# driver-power-stage.net
KiCad netlist of a schematic drawn in Altium Designer
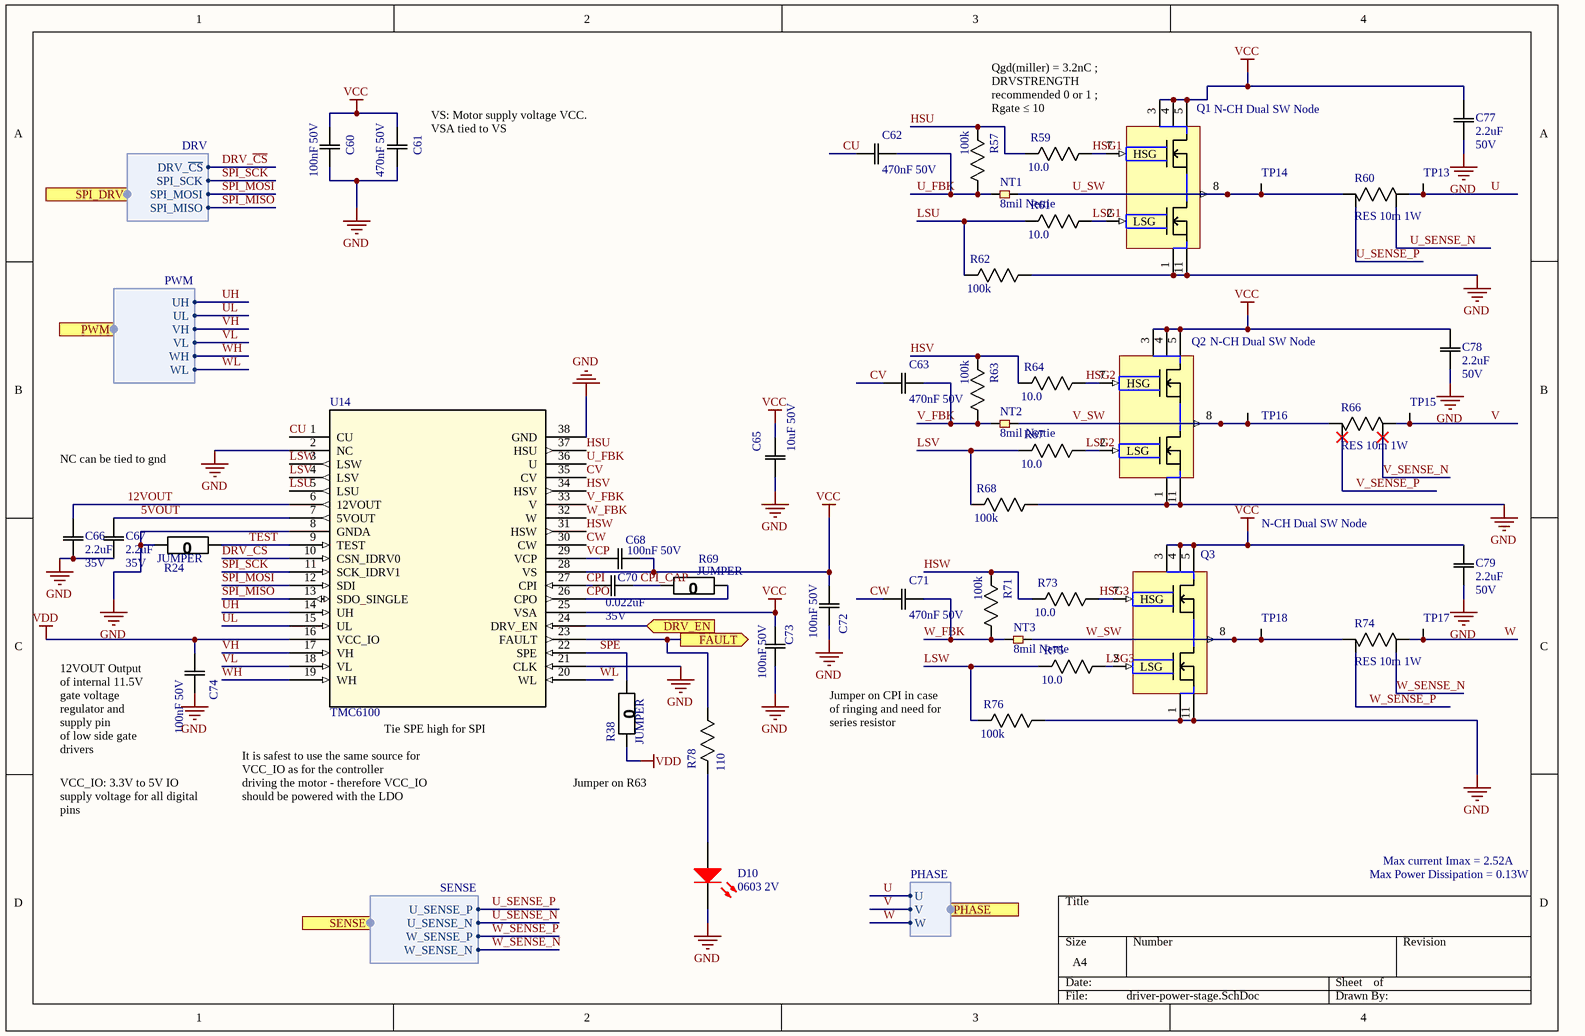
[diagram p0: driver-power-stage.SchDoc]

(export (version "E")
  (design (tool "Eeschema 10.0.6"))
  (components
    (comp (ref "C60")
      (value "100nF 50V")
      (footprint "0603")
      (description "Default Symbol for Capacitors")
      (fields (field (name "TOLERANCE") "10%") (field (name "PART NUMBER") "CAP 100nF 50V"))
      (libsource (lib "capacitor_library") (part "CAP_Default"))
    )
    (comp (ref "C61")
      (value "470nF 50V")
      (footprint "0603")
      (description "Default Symbol for Capacitors")
      (fields (field (name "TOLERANCE") "10%") (field (name "PART NUMBER") "CAP 470nF 50V"))
      (libsource (lib "capacitor_library") (part "CAP_Default"))
    )
    (comp (ref "C62")
      (value "470nF 50V")
      (footprint "0603")
      (description "Default Symbol for Capacitors")
      (fields (field (name "TOLERANCE") "10%") (field (name "PART NUMBER") "CAP 470nF 50V"))
      (libsource (lib "capacitor_library") (part "CAP_Default"))
    )
    (comp (ref "C63")
      (value "470nF 50V")
      (footprint "0603")
      (description "Default Symbol for Capacitors")
      (fields (field (name "TOLERANCE") "10%") (field (name "PART NUMBER") "CAP 470nF 50V"))
      (libsource (lib "capacitor_library") (part "CAP_Default"))
    )
    (comp (ref "C65")
      (value "10uF 50V")
      (footprint "0805")
      (description "Default Symbol for Capacitors")
      (fields (field (name "TOLERANCE") "10%") (field (name "PART NUMBER") "CAP 10uF 50V"))
      (libsource (lib "capacitor_library") (part "CAP_Default"))
    )
    (comp (ref "C66")
      (value "2.2uF")
      (footprint "0603")
      (description "Default Symbol for Capacitors")
      (fields
        (field (name "TOLERANCE") "10%")
        (field (name "RATING") "35V")
        (field (name "PART NUMBER") "CAP 2.2uF 35V")
      )
      (libsource (lib "capacitor_library") (part "CAP_Default"))
    )
    (comp (ref "C67")
      (value "2.2uF")
      (footprint "0603")
      (description "Default Symbol for Capacitors")
      (fields
        (field (name "TOLERANCE") "10%")
        (field (name "RATING") "35V")
        (field (name "PART NUMBER") "CAP 2.2uF 35V")
      )
      (libsource (lib "capacitor_library") (part "CAP_Default"))
    )
    (comp (ref "C68")
      (value "100nF 50V")
      (footprint "0603")
      (description "Default Symbol for Capacitors")
      (fields (field (name "TOLERANCE") "10%") (field (name "PART NUMBER") "CAP 100nF 50V"))
      (libsource (lib "capacitor_library") (part "CAP_Default"))
    )
    (comp (ref "C70")
      (value "0.022uF")
      (footprint "0603")
      (description "Default Symbol for Capacitors")
      (fields
        (field (name "TOLERANCE") "10%")
        (field (name "RATING") "35V")
        (field (name "PART NUMBER") "CAP 0.022uF 35V")
      )
      (libsource (lib "capacitor_library") (part "CAP_Default"))
    )
    (comp (ref "C71")
      (value "470nF 50V")
      (footprint "0603")
      (description "Default Symbol for Capacitors")
      (fields (field (name "TOLERANCE") "10%") (field (name "PART NUMBER") "CAP 470nF 50V"))
      (libsource (lib "capacitor_library") (part "CAP_Default"))
    )
    (comp (ref "C72")
      (value "100nF 50V")
      (footprint "0603")
      (description "Default Symbol for Capacitors")
      (fields (field (name "TOLERANCE") "10%") (field (name "PART NUMBER") "CAP 100nF 50V"))
      (libsource (lib "capacitor_library") (part "CAP_Default"))
    )
    (comp (ref "C73")
      (value "100nF 50V")
      (footprint "0603")
      (description "Default Symbol for Capacitors")
      (fields (field (name "TOLERANCE") "10%") (field (name "PART NUMBER") "CAP 100nF 50V"))
      (libsource (lib "capacitor_library") (part "CAP_Default"))
    )
    (comp (ref "C74")
      (value "100nF 50V")
      (footprint "0603")
      (description "Default Symbol for Capacitors")
      (fields (field (name "TOLERANCE") "10%") (field (name "PART NUMBER") "CAP 100nF 50V"))
      (libsource (lib "capacitor_library") (part "CAP_Default"))
    )
    (comp (ref "C77")
      (value "2.2uF")
      (footprint "0603")
      (description "CAP CER 2.2UF 50V X5R 0603/0805")
      (fields
        (field (name "TOLERANCE") "10%")
        (field (name "RATING") "50V")
        (field (name "PART NUMBER") "CAP 2.2uF 50V")
      )
      (libsource (lib "capacitor_library") (part "CAP 2.2uF 50V"))
    )
    (comp (ref "C78")
      (value "2.2uF")
      (footprint "0603")
      (description "CAP CER 2.2UF 50V X5R 0603/0805")
      (fields
        (field (name "TOLERANCE") "10%")
        (field (name "RATING") "50V")
        (field (name "PART NUMBER") "CAP 2.2uF 50V")
      )
      (libsource (lib "capacitor_library") (part "CAP 2.2uF 50V"))
    )
    (comp (ref "C79")
      (value "2.2uF")
      (footprint "0603")
      (description "CAP CER 2.2UF 50V X5R 0603/0805")
      (fields
        (field (name "TOLERANCE") "10%")
        (field (name "RATING") "50V")
        (field (name "PART NUMBER") "CAP 2.2uF 50V")
      )
      (libsource (lib "capacitor_library") (part "CAP 2.2uF 50V"))
    )
    (comp (ref "D10")
      (value "0603 2V")
      (footprint "0603 - LED2")
      (description "0603 red led alingap 631nm-639nm water clear 18-180mcd 130d")
      (fields (field (name "PART NUMBER") "LED RED SMD 0603"))
      (libsource (lib "Diode_Library") (part "LED RED SMD 0603"))
    )
    (comp (ref "NT1")
      (value "8mil Nettie")
      (footprint "NT_8mil")
      (description "8mil wide nettie")
      (fields (field (name "PART NUMBER") "NT_8"))
      (libsource (lib "Resistor_Library") (part "NT_8"))
    )
    (comp (ref "NT2")
      (value "8mil Nettie")
      (footprint "NT_8mil")
      (description "8mil wide nettie")
      (fields (field (name "PART NUMBER") "NT_8"))
      (libsource (lib "Resistor_Library") (part "NT_8"))
    )
    (comp (ref "NT3")
      (value "8mil Nettie")
      (footprint "NT_8mil")
      (description "8mil wide nettie")
      (fields (field (name "PART NUMBER") "NT_8"))
      (libsource (lib "Resistor_Library") (part "NT_8"))
    )
    (comp (ref "Q1")
      (value "N-CH Dual SW Node")
      (footprint "12-PowerWQFN")
      (description "MOSFET N+N COMMON PHASE SW 40V 60A")
      (fields (field (name "PART NUMBER") "MOSFET N-CH DUAL NTTFD4D0N04HLTWG"))
      (libsource (lib "Transistor_Library") (part "MOSFET N-CH DUAL NTTFD4D0N04HLTWG"))
    )
    (comp (ref "Q2")
      (value "N-CH Dual SW Node")
      (footprint "12-PowerWQFN")
      (description "MOSFET N+N COMMON PHASE SW 40V 60A")
      (fields (field (name "PART NUMBER") "MOSFET N-CH DUAL NTTFD4D0N04HLTWG"))
      (libsource (lib "Transistor_Library") (part "MOSFET N-CH DUAL NTTFD4D0N04HLTWG"))
    )
    (comp (ref "Q3")
      (value "N-CH Dual SW Node")
      (footprint "12-PowerWQFN")
      (description "MOSFET N+N COMMON PHASE SW 40V 60A")
      (fields (field (name "PART NUMBER") "MOSFET N-CH DUAL NTTFD4D0N04HLTWG"))
      (libsource (lib "Transistor_Library") (part "MOSFET N-CH DUAL NTTFD4D0N04HLTWG"))
    )
    (comp (ref "R24")
      (value "JUMPER")
      (footprint "0603")
      (description "RES SMD 0 OHM JUMPER GENERIC 0805")
      (fields (field (name "PART NUMBER") "RES 0 JUMPER"))
      (libsource (lib "Resistor_Library") (part "RES 0 JUMPER"))
    )
    (comp (ref "R38")
      (value "JUMPER")
      (footprint "0603")
      (description "RES SMD 0 OHM JUMPER GENERIC 0805")
      (fields (field (name "PART NUMBER") "RES 0 JUMPER"))
      (libsource (lib "Resistor_Library") (part "RES 0 JUMPER"))
    )
    (comp (ref "R57")
      (value "100k")
      (footprint "0603")
      (description "RES SMD 100K OHM 5% 1/8W 0805")
      (fields (field (name "TOLERANCE") "5%") (field (name "PART NUMBER") "RES 100k 1/8W 5%"))
      (libsource (lib "Resistor_Library") (part "RES_DEFAULT"))
    )
    (comp (ref "R59")
      (value "10.0")
      (footprint "0603")
      (description "Default Resistor Symbol")
      (fields (field (name "TOLERANCE") "1%") (field (name "PART NUMBER") "RES 10.0 1/8W - 1%"))
      (libsource (lib "Resistor_Library") (part "RES_DEFAULT"))
    )
    (comp (ref "R60")
      (value "RES 10m 1W")
      (footprint "1206 - Current Sense")
      (description "RES SMD 0.01 OHM 1% 1W 1206")
      (fields (field (name "TOLERANCE") "1%"))
      (libsource (lib "Resistor_Library") (part "RES 10m 1W"))
    )
    (comp (ref "R61")
      (value "10.0")
      (footprint "0603")
      (description "Default Resistor Symbol")
      (fields (field (name "TOLERANCE") "1%") (field (name "PART NUMBER") "RES 10.0 1/8W - 1%"))
      (libsource (lib "Resistor_Library") (part "RES_DEFAULT"))
    )
    (comp (ref "R62")
      (value "100k")
      (footprint "0603")
      (description "RES SMD 100K OHM 5% 1/8W 0805")
      (fields (field (name "TOLERANCE") "5%") (field (name "PART NUMBER") "RES 100k 1/8W 5%"))
      (libsource (lib "Resistor_Library") (part "RES_DEFAULT"))
    )
    (comp (ref "R63")
      (value "100k")
      (footprint "0603")
      (description "RES SMD 100K OHM 5% 1/8W 0805")
      (fields (field (name "TOLERANCE") "5%") (field (name "PART NUMBER") "RES 100k 1/8W 5%"))
      (libsource (lib "Resistor_Library") (part "RES_DEFAULT"))
    )
    (comp (ref "R64")
      (value "10.0")
      (footprint "0603")
      (description "Default Resistor Symbol")
      (fields (field (name "TOLERANCE") "1%") (field (name "PART NUMBER") "RES 10.0 1/8W - 1%"))
      (libsource (lib "") (part "RES_DEFAULT_1"))
    )
    (comp (ref "R66")
      (value "RES 10m 1W")
      (footprint "1206 - Current Sense")
      (description "RES SMD 0.01 OHM 1% 1W 1206")
      (fields (field (name "TOLERANCE") "1%"))
      (libsource (lib "Resistor_Library") (part "RES 10m 1W"))
    )
    (comp (ref "R67")
      (value "10.0")
      (footprint "0603")
      (description "Default Resistor Symbol")
      (fields (field (name "TOLERANCE") "1%") (field (name "PART NUMBER") "RES 10.0 1/8W - 1%"))
      (libsource (lib "Resistor_Library") (part "RES_DEFAULT"))
    )
    (comp (ref "R68")
      (value "100k")
      (footprint "0603")
      (description "RES SMD 100K OHM 5% 1/8W 0805")
      (fields (field (name "TOLERANCE") "5%") (field (name "PART NUMBER") "RES 100k 1/8W 5%"))
      (libsource (lib "Resistor_Library") (part "RES_DEFAULT"))
    )
    (comp (ref "R69")
      (value "JUMPER")
      (footprint "0603")
      (description "RES SMD 0 OHM JUMPER GENERIC 0805")
      (fields (field (name "PART NUMBER") "RES 0 JUMPER"))
      (libsource (lib "Resistor_Library") (part "RES 0 JUMPER"))
    )
    (comp (ref "R71")
      (value "100k")
      (footprint "0603")
      (description "RES SMD 100K OHM 5% 1/8W 0805")
      (fields (field (name "TOLERANCE") "5%") (field (name "PART NUMBER") "RES 100k 1/8W 5%"))
      (libsource (lib "Resistor_Library") (part "RES_DEFAULT"))
    )
    (comp (ref "R73")
      (value "10.0")
      (footprint "0603")
      (description "Default Resistor Symbol")
      (fields (field (name "TOLERANCE") "1%") (field (name "PART NUMBER") "RES 10.0 1/8W - 1%"))
      (libsource (lib "") (part "RES_DEFAULT_1"))
    )
    (comp (ref "R74")
      (value "RES 10m 1W")
      (footprint "1206 - Current Sense")
      (description "RES SMD 0.01 OHM 1% 1W 1206")
      (fields (field (name "TOLERANCE") "1%"))
      (libsource (lib "Resistor_Library") (part "RES 10m 1W"))
    )
    (comp (ref "R75")
      (value "10.0")
      (footprint "0603")
      (description "Default Resistor Symbol")
      (fields (field (name "TOLERANCE") "1%") (field (name "PART NUMBER") "RES 10.0 1/8W - 1%"))
      (libsource (lib "") (part "RES_DEFAULT_1"))
    )
    (comp (ref "R76")
      (value "100k")
      (footprint "0603")
      (description "RES SMD 100K OHM 5% 1/8W 0805")
      (fields (field (name "TOLERANCE") "5%") (field (name "PART NUMBER") "RES 100k 1/8W 5%"))
      (libsource (lib "Resistor_Library") (part "RES_DEFAULT"))
    )
    (comp (ref "R78")
      (value "110")
      (footprint "0603")
      (description "Default Resistor Symbol")
      (fields (field (name "TOLERANCE") "1%") (field (name "PART NUMBER") "RES 110.0 1/8W - 1%"))
      (libsource (lib "Resistor_Library") (part "RES_DEFAULT"))
    )
    (comp (ref "TP13")
      (value "U_SL")
      (footprint "TP")
      (fields (field (name "PART NUMBER") "Test Point (Via)"))
      (libsource (lib "IC_Library") (part "Test Point (Via)"))
    )
    (comp (ref "TP14")
      (value "U_SH")
      (footprint "TP")
      (fields (field (name "PART NUMBER") "Test Point (Via)"))
      (libsource (lib "IC_Library") (part "Test Point (Via)"))
    )
    (comp (ref "TP15")
      (value "V_SL")
      (footprint "TP")
      (fields (field (name "PART NUMBER") "Test Point (Via)"))
      (libsource (lib "IC_Library") (part "Test Point (Via)"))
    )
    (comp (ref "TP16")
      (value "V_SH")
      (footprint "TP")
      (fields (field (name "PART NUMBER") "Test Point (Via)"))
      (libsource (lib "IC_Library") (part "Test Point (Via)"))
    )
    (comp (ref "TP17")
      (value "W_SL")
      (footprint "TP")
      (fields (field (name "PART NUMBER") "Test Point (Via)"))
      (libsource (lib "IC_Library") (part "Test Point (Via)"))
    )
    (comp (ref "TP18")
      (value "W_SH")
      (footprint "TP")
      (fields (field (name "PART NUMBER") "Test Point (Via)"))
      (libsource (lib "IC_Library") (part "Test Point (Via)"))
    )
    (comp (ref "U14")
      (value "TMC6100")
      (footprint "QFN50P700X700X85_HS-38N")
      (description "GATE DRIVER IC 8-60V QFN37")
      (libsource (lib "IC_Library") (part "TMC6100"))
    )
  )
  (nets
    (net (code "5") (name "/5VOUT") (class "Default")
      (node (ref "C67") (pin "2") (pinfunction "C2_2") (pintype "passive"))
      (node (ref "U14") (pin "7") (pinfunction "5VOUT_7") (pintype "output"))
    )
    (net (code "6") (name "/12VOUT") (class "Default")
      (node (ref "C66") (pin "2") (pinfunction "C2_2") (pintype "passive"))
      (node (ref "U14") (pin "6") (pinfunction "12VOUT_6") (pintype "output"))
    )
    (net (code "7") (name "/CPI") (class "Default")
      (node (ref "C70") (pin "1") (pinfunction "C1_1") (pintype "passive"))
      (node (ref "U14") (pin "27") (pinfunction "CPI_27") (pintype "input"))
    )
    (net (code "8") (name "/CPI_CAP") (class "Default")
      (node (ref "C70") (pin "2") (pinfunction "C2_2") (pintype "passive"))
      (node (ref "R69") (pin "2") (pinfunction "R2_2") (pintype "passive"))
    )
    (net (code "9") (name "/CPO") (class "Default")
      (node (ref "R69") (pin "1") (pinfunction "R1_1") (pintype "passive"))
      (node (ref "U14") (pin "26") (pinfunction "CPO_26") (pintype "output"))
    )
    (net (code "10") (name "/CU") (class "Default")
      (node (ref "C62") (pin "1") (pinfunction "C1_1") (pintype "passive"))
      (node (ref "U14") (pin "1") (pinfunction "CU_1") (pintype "passive"))
    )
    (net (code "11") (name "/CV") (class "Default")
      (node (ref "C63") (pin "1") (pinfunction "C1_1") (pintype "passive"))
      (node (ref "U14") (pin "35") (pinfunction "CV_35") (pintype "passive"))
    )
    (net (code "12") (name "/CW") (class "Default")
      (node (ref "C71") (pin "1") (pinfunction "C1_1") (pintype "passive"))
      (node (ref "U14") (pin "30") (pinfunction "CW_30") (pintype "passive"))
    )
    (net (code "13") (name "/DRV_EN") (class "Default")
      (node (ref "U14") (pin "24") (pinfunction "DRV_EN_24") (pintype "input"))
    )
    (net (code "14") (name "/DRV_~{CS}") (class "Default")
      (node (ref "U14") (pin "10") (pinfunction "CSN_IDRV0_10") (pintype "input"))
    )
    (net (code "15") (name "/FAULT") (class "Default")
      (node (ref "R78") (pin "1") (pinfunction "R1_1") (pintype "passive"))
      (node (ref "U14") (pin "23") (pinfunction "FAULT_23") (pintype "output"))
    )
    (net (code "16") (name "/HSG1") (class "Default")
      (node (ref "Q1") (pin "7") (pinfunction "HSG_7") (pintype "input"))
      (node (ref "R59") (pin "1") (pinfunction "R1_1") (pintype "passive"))
    )
    (net (code "17") (name "/HSG2") (class "Default")
      (node (ref "Q2") (pin "7") (pinfunction "HSG_7") (pintype "input"))
      (node (ref "R64") (pin "1") (pinfunction "R1_1") (pintype "passive"))
    )
    (net (code "18") (name "/HSG3") (class "Default")
      (node (ref "Q3") (pin "7") (pinfunction "HSG_7") (pintype "input"))
      (node (ref "R73") (pin "1") (pinfunction "R1_1") (pintype "passive"))
    )
    (net (code "19") (name "/HSU") (class "Default")
      (node (ref "R57") (pin "2") (pinfunction "R2_2") (pintype "passive"))
      (node (ref "R59") (pin "2") (pinfunction "R2_2") (pintype "passive"))
      (node (ref "U14") (pin "37") (pinfunction "HSU_37") (pintype "output"))
    )
    (net (code "20") (name "/HSV") (class "Default")
      (node (ref "R63") (pin "2") (pinfunction "R2_2") (pintype "passive"))
      (node (ref "R64") (pin "2") (pinfunction "R2_2") (pintype "passive"))
      (node (ref "U14") (pin "34") (pinfunction "HSV_34") (pintype "output"))
    )
    (net (code "21") (name "/HSW") (class "Default")
      (node (ref "R71") (pin "2") (pinfunction "R2_2") (pintype "passive"))
      (node (ref "R73") (pin "2") (pinfunction "R2_2") (pintype "passive"))
      (node (ref "U14") (pin "31") (pinfunction "HSW_31") (pintype "output"))
    )
    (net (code "22") (name "/LSG1") (class "Default")
      (node (ref "Q1") (pin "2") (pinfunction "LSG_2") (pintype "input"))
      (node (ref "R61") (pin "1") (pinfunction "R1_1") (pintype "passive"))
    )
    (net (code "23") (name "/LSG2") (class "Default")
      (node (ref "Q2") (pin "2") (pinfunction "LSG_2") (pintype "input"))
      (node (ref "R67") (pin "1") (pinfunction "R1_1") (pintype "passive"))
    )
    (net (code "24") (name "/LSG3") (class "Default")
      (node (ref "Q3") (pin "2") (pinfunction "LSG_2") (pintype "input"))
      (node (ref "R75") (pin "1") (pinfunction "R1_1") (pintype "passive"))
    )
    (net (code "25") (name "/LSU") (class "Default")
      (node (ref "R61") (pin "2") (pinfunction "R2_2") (pintype "passive"))
      (node (ref "R62") (pin "2") (pinfunction "R2_2") (pintype "passive"))
      (node (ref "U14") (pin "5") (pinfunction "LSU_5") (pintype "output"))
    )
    (net (code "26") (name "/LSV") (class "Default")
      (node (ref "R67") (pin "2") (pinfunction "R2_2") (pintype "passive"))
      (node (ref "R68") (pin "2") (pinfunction "R2_2") (pintype "passive"))
      (node (ref "U14") (pin "4") (pinfunction "LSV_4") (pintype "output"))
    )
    (net (code "27") (name "/LSW") (class "Default")
      (node (ref "R75") (pin "2") (pinfunction "R2_2") (pintype "passive"))
      (node (ref "R76") (pin "2") (pinfunction "R2_2") (pintype "passive"))
      (node (ref "U14") (pin "3") (pinfunction "LSW_3") (pintype "output"))
    )
    (net (code "28") (name "/SPE") (class "Default")
      (node (ref "R38") (pin "1") (pinfunction "R1_1") (pintype "passive"))
      (node (ref "U14") (pin "22") (pinfunction "SPE_22") (pintype "input"))
    )
    (net (code "29") (name "/SPI_MISO") (class "Default")
      (node (ref "U14") (pin "13") (pinfunction "SDO_SINGLE_13") (pintype "bidirectional"))
    )
    (net (code "30") (name "/SPI_MOSI") (class "Default")
      (node (ref "U14") (pin "12") (pinfunction "SDI_12") (pintype "input"))
    )
    (net (code "31") (name "/SPI_SCK") (class "Default")
      (node (ref "U14") (pin "11") (pinfunction "SCK_IDRV1_11") (pintype "input"))
    )
    (net (code "32") (name "/TEST") (class "Default")
      (node (ref "R24") (pin "1") (pinfunction "R1_1") (pintype "passive"))
      (node (ref "U14") (pin "9") (pinfunction "TEST_9") (pintype "input"))
    )
    (net (code "33") (name "/U") (class "Default")
      (node (ref "R60") (pin "1") (pinfunction "1_1") (pintype "passive"))
      (node (ref "TP13") (pin "1") (pinfunction "1_1") (pintype "passive"))
    )
    (net (code "34") (name "/UH") (class "Default")
      (node (ref "U14") (pin "14") (pinfunction "UH_14") (pintype "input"))
    )
    (net (code "35") (name "/UL") (class "Default")
      (node (ref "U14") (pin "15") (pinfunction "UL_15") (pintype "input"))
    )
    (net (code "36") (name "/U_FBK") (class "Default")
      (node (ref "C62") (pin "2") (pinfunction "C2_2") (pintype "passive"))
      (node (ref "NT1") (pin "1") (pinfunction "1_1") (pintype "passive"))
      (node (ref "R57") (pin "1") (pinfunction "R1_1") (pintype "passive"))
      (node (ref "U14") (pin "36") (pinfunction "U_36") (pintype "passive"))
    )
    (net (code "37") (name "/U_SENSE_N") (class "Default")
      (node (ref "R60") (pin "S1") (pinfunction "S1_S1") (pintype "passive"))
    )
    (net (code "38") (name "/U_SENSE_P") (class "Default")
      (node (ref "R60") (pin "S2") (pinfunction "S2_S2") (pintype "passive"))
    )
    (net (code "39") (name "/U_SW") (class "Default")
      (node (ref "NT1") (pin "2") (pinfunction "2_2") (pintype "passive"))
      (node (ref "Q1") (pin "8") (pinfunction "SW_8") (pintype "output"))
      (node (ref "R60") (pin "2") (pinfunction "2_2") (pintype "passive"))
      (node (ref "TP14") (pin "1") (pinfunction "1_1") (pintype "passive"))
    )
    (net (code "40") (name "/V") (class "Default")
      (node (ref "R66") (pin "1") (pinfunction "1_1") (pintype "passive"))
      (node (ref "TP15") (pin "1") (pinfunction "1_1") (pintype "passive"))
    )
    (net (code "41") (name "/VCP") (class "Default")
      (node (ref "C68") (pin "1") (pinfunction "C1_1") (pintype "passive"))
      (node (ref "U14") (pin "29") (pinfunction "VCP_29") (pintype "power_in"))
    )
    (net (code "42") (name "/VH") (class "Default")
      (node (ref "U14") (pin "17") (pinfunction "VH_17") (pintype "input"))
    )
    (net (code "43") (name "/VL") (class "Default")
      (node (ref "U14") (pin "18") (pinfunction "VL_18") (pintype "input"))
    )
    (net (code "44") (name "/V_FBK") (class "Default")
      (node (ref "C63") (pin "2") (pinfunction "C2_2") (pintype "passive"))
      (node (ref "NT2") (pin "1") (pinfunction "1_1") (pintype "passive"))
      (node (ref "R63") (pin "1") (pinfunction "R1_1") (pintype "passive"))
      (node (ref "U14") (pin "33") (pinfunction "V_33") (pintype "passive"))
    )
    (net (code "45") (name "/V_SENSE_N") (class "Default")
      (node (ref "R66") (pin "S1") (pinfunction "S1_S1") (pintype "passive+no_connect"))
    )
    (net (code "46") (name "/V_SENSE_P") (class "Default")
      (node (ref "R66") (pin "S2") (pinfunction "S2_S2") (pintype "passive+no_connect"))
    )
    (net (code "47") (name "/V_SW") (class "Default")
      (node (ref "NT2") (pin "2") (pinfunction "2_2") (pintype "passive"))
      (node (ref "Q2") (pin "8") (pinfunction "SW_8") (pintype "output"))
      (node (ref "R66") (pin "2") (pinfunction "2_2") (pintype "passive"))
      (node (ref "TP16") (pin "1") (pinfunction "1_1") (pintype "passive"))
    )
    (net (code "48") (name "/W") (class "Default")
      (node (ref "R74") (pin "1") (pinfunction "1_1") (pintype "passive"))
      (node (ref "TP17") (pin "1") (pinfunction "1_1") (pintype "passive"))
    )
    (net (code "49") (name "/WH") (class "Default")
      (node (ref "U14") (pin "19") (pinfunction "WH_19") (pintype "input"))
    )
    (net (code "50") (name "/WL") (class "Default")
      (node (ref "U14") (pin "20") (pinfunction "WL_20") (pintype "input"))
    )
    (net (code "51") (name "/W_FBK") (class "Default")
      (node (ref "C71") (pin "2") (pinfunction "C2_2") (pintype "passive"))
      (node (ref "NT3") (pin "1") (pinfunction "1_1") (pintype "passive"))
      (node (ref "R71") (pin "1") (pinfunction "R1_1") (pintype "passive"))
      (node (ref "U14") (pin "32") (pinfunction "W_32") (pintype "passive"))
    )
    (net (code "52") (name "/W_SENSE_N") (class "Default")
      (node (ref "R74") (pin "S1") (pinfunction "S1_S1") (pintype "passive"))
    )
    (net (code "53") (name "/W_SENSE_P") (class "Default")
      (node (ref "R74") (pin "S2") (pinfunction "S2_S2") (pintype "passive"))
    )
    (net (code "54") (name "/W_SW") (class "Default")
      (node (ref "NT3") (pin "2") (pinfunction "2_2") (pintype "passive"))
      (node (ref "Q3") (pin "8") (pinfunction "SW_8") (pintype "output"))
      (node (ref "R74") (pin "2") (pinfunction "2_2") (pintype "passive"))
      (node (ref "TP18") (pin "1") (pinfunction "1_1") (pintype "passive"))
    )
    (net (code "59") (name "GND") (class "Default")
      (node (ref "C60") (pin "2") (pinfunction "C2_2") (pintype "passive"))
      (node (ref "C61") (pin "2") (pinfunction "C2_2") (pintype "passive"))
      (node (ref "C65") (pin "1") (pinfunction "C1_1") (pintype "passive"))
      (node (ref "C66") (pin "1") (pinfunction "C1_1") (pintype "passive"))
      (node (ref "C67") (pin "1") (pinfunction "C1_1") (pintype "passive"))
      (node (ref "C72") (pin "2") (pinfunction "C2_2") (pintype "passive"))
      (node (ref "C73") (pin "2") (pinfunction "C2_2") (pintype "passive"))
      (node (ref "C74") (pin "2") (pinfunction "C2_2") (pintype "passive"))
      (node (ref "C77") (pin "1") (pinfunction "C1_1") (pintype "passive"))
      (node (ref "C78") (pin "1") (pinfunction "C1_1") (pintype "passive"))
      (node (ref "C79") (pin "1") (pinfunction "C1_1") (pintype "passive"))
      (node (ref "D10") (pin "2") (pinfunction "K_2") (pintype "passive"))
      (node (ref "Q1") (pin "1") (pinfunction "GND_1") (pintype "power_in"))
      (node (ref "Q1") (pin "11") (pinfunction "GND_11") (pintype "power_in"))
      (node (ref "Q2") (pin "1") (pinfunction "GND_1") (pintype "power_in"))
      (node (ref "Q2") (pin "11") (pinfunction "GND_11") (pintype "power_in"))
      (node (ref "Q3") (pin "1") (pinfunction "GND_1") (pintype "power_in"))
      (node (ref "Q3") (pin "11") (pinfunction "GND_11") (pintype "power_in"))
      (node (ref "R24") (pin "2") (pinfunction "R2_2") (pintype "passive"))
      (node (ref "R62") (pin "1") (pinfunction "R1_1") (pintype "passive"))
      (node (ref "R68") (pin "1") (pinfunction "R1_1") (pintype "passive"))
      (node (ref "R76") (pin "1") (pinfunction "R1_1") (pintype "passive"))
      (node (ref "U14") (pin "2") (pinfunction "NC_2") (pintype "passive"))
      (node (ref "U14") (pin "21") (pinfunction "CLK_21") (pintype "input"))
      (node (ref "U14") (pin "38") (pinfunction "GND_38") (pintype "passive"))
      (node (ref "U14") (pin "8") (pinfunction "GNDA_8") (pintype "power_in"))
    )
    (net (code "60") (name "Net-(D10-A)") (class "Default")
      (node (ref "D10") (pin "1") (pinfunction "A_1") (pintype "passive"))
      (node (ref "R78") (pin "2") (pinfunction "R2_2") (pintype "passive"))
    )
    (net (code "61") (name "VCC") (class "Default")
      (node (ref "C60") (pin "1") (pinfunction "C1_1") (pintype "passive"))
      (node (ref "C61") (pin "1") (pinfunction "C1_1") (pintype "passive"))
      (node (ref "C65") (pin "2") (pinfunction "C2_2") (pintype "passive"))
      (node (ref "C68") (pin "2") (pinfunction "C2_2") (pintype "passive"))
      (node (ref "C72") (pin "1") (pinfunction "C1_1") (pintype "passive"))
      (node (ref "C73") (pin "1") (pinfunction "C1_1") (pintype "passive"))
      (node (ref "C77") (pin "2") (pinfunction "C2_2") (pintype "passive"))
      (node (ref "C78") (pin "2") (pinfunction "C2_2") (pintype "passive"))
      (node (ref "C79") (pin "2") (pinfunction "C2_2") (pintype "passive"))
      (node (ref "Q1") (pin "3") (pinfunction "V+_3") (pintype "power_in"))
      (node (ref "Q1") (pin "4") (pinfunction "V+_4") (pintype "power_in"))
      (node (ref "Q1") (pin "5") (pinfunction "V+_5") (pintype "power_in"))
      (node (ref "Q2") (pin "3") (pinfunction "V+_3") (pintype "power_in"))
      (node (ref "Q2") (pin "4") (pinfunction "V+_4") (pintype "power_in"))
      (node (ref "Q2") (pin "5") (pinfunction "V+_5") (pintype "power_in"))
      (node (ref "Q3") (pin "3") (pinfunction "V+_3") (pintype "power_in"))
      (node (ref "Q3") (pin "4") (pinfunction "V+_4") (pintype "power_in"))
      (node (ref "Q3") (pin "5") (pinfunction "V+_5") (pintype "power_in"))
      (node (ref "U14") (pin "25") (pinfunction "VSA_25") (pintype "power_in"))
      (node (ref "U14") (pin "28") (pinfunction "VS_28") (pintype "power_in"))
    )
    (net (code "62") (name "VDD") (class "Default")
      (node (ref "C74") (pin "1") (pinfunction "C1_1") (pintype "passive"))
      (node (ref "R38") (pin "2") (pinfunction "R2_2") (pintype "passive"))
      (node (ref "U14") (pin "16") (pinfunction "VCC_IO_16") (pintype "power_in"))
    )
  )
)
